# Smart_Driver_Circuit.net
KiCad netlist of a schematic drawn in Altium Designer
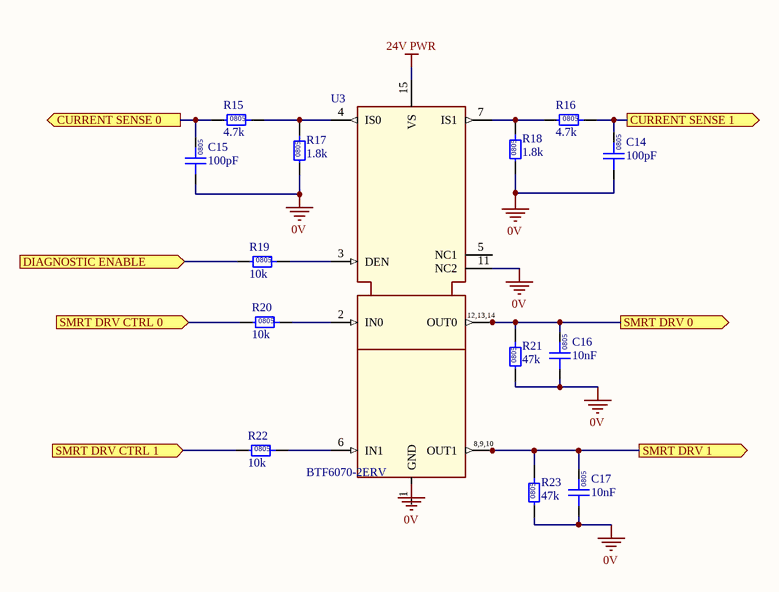
[diagram p0: Smart Driver Circuit.SchDoc]

(export (version "E")
  (design (tool "Eeschema 10.0.6"))
  (components
    (comp (ref "C14")
      (value "100pF")
      (footprint "0805")
      (fields
        (field (name "PART NUMBER") "GCM2165C1H101JA16D")
        (field (name "MANUFACTURER") "muRata")
        (field (name "TOLERANCE") "±5%")
      )
      (libsource (lib "ts_standard_library") (part "Capacitor 0805"))
    )
    (comp (ref "C15")
      (value "100pF")
      (footprint "0805")
      (fields
        (field (name "PART NUMBER") "GCM2165C1H101JA16D")
        (field (name "MANUFACTURER") "muRata")
        (field (name "TOLERANCE") "±5%")
      )
      (libsource (lib "ts_standard_library") (part "Capacitor 0805"))
    )
    (comp (ref "C16")
      (value "10nF")
      (footprint "0805")
      (fields
        (field (name "PART NUMBER") "GCM2195C1H103JA16D")
        (field (name "MANUFACTURER") "muRata")
        (field (name "TOLERANCE") "±5%")
      )
      (libsource (lib "ts_standard_library") (part "Capacitor 0805"))
    )
    (comp (ref "C17")
      (value "10nF")
      (footprint "0805")
      (fields
        (field (name "PART NUMBER") "GCM2195C1H103JA16D")
        (field (name "MANUFACTURER") "muRata")
        (field (name "TOLERANCE") "±5%")
      )
      (libsource (lib "ts_standard_library") (part "Capacitor 0805"))
    )
    (comp (ref "R15")
      (value "4.7k")
      (footprint "0805")
      (fields
        (field (name "PART NUMBER") "RC0805FR074K7L")
        (field (name "MANUFACTURER") "YAGEO")
        (field (name "TOLERANCE") "0.01")
      )
      (libsource (lib "ts_standard_library") (part "Resistor 0805"))
    )
    (comp (ref "R16")
      (value "4.7k")
      (footprint "0805")
      (fields
        (field (name "PART NUMBER") "RC0805FR074K7L")
        (field (name "MANUFACTURER") "YAGEO")
        (field (name "TOLERANCE") "0.01")
      )
      (libsource (lib "ts_standard_library") (part "Resistor 0805"))
    )
    (comp (ref "R17")
      (value "1.8k")
      (footprint "0805")
      (fields
        (field (name "PART NUMBER") "RC0805FR071K8L")
        (field (name "MANUFACTURER") "YAGEO")
        (field (name "TOLERANCE") "0.01")
      )
      (libsource (lib "ts_standard_library") (part "Resistor 0805"))
    )
    (comp (ref "R18")
      (value "1.8k")
      (footprint "0805")
      (fields
        (field (name "PART NUMBER") "RC0805FR071K8L")
        (field (name "MANUFACTURER") "YAGEO")
        (field (name "TOLERANCE") "0.01")
      )
      (libsource (lib "ts_standard_library") (part "Resistor 0805"))
    )
    (comp (ref "R19")
      (value "10k")
      (footprint "0805")
      (fields
        (field (name "PART NUMBER") "RC0805FR0710KL")
        (field (name "MANUFACTURER") "YAGEO")
        (field (name "TOLERANCE") "0.01")
      )
      (libsource (lib "ts_standard_library") (part "Resistor 0805"))
    )
    (comp (ref "R20")
      (value "10k")
      (footprint "0805")
      (fields
        (field (name "PART NUMBER") "RC0805FR0710KL")
        (field (name "MANUFACTURER") "YAGEO")
        (field (name "TOLERANCE") "0.01")
      )
      (libsource (lib "ts_standard_library") (part "Resistor 0805"))
    )
    (comp (ref "R21")
      (value "47k")
      (footprint "0805")
      (fields
        (field (name "PART NUMBER") "RC0805FR0747KL")
        (field (name "MANUFACTURER") "YAGEO")
        (field (name "TOLERANCE") "0.01")
      )
      (libsource (lib "ts_standard_library") (part "Resistor 0805"))
    )
    (comp (ref "R22")
      (value "10k")
      (footprint "0805")
      (fields
        (field (name "PART NUMBER") "RC0805FR0710KL")
        (field (name "MANUFACTURER") "YAGEO")
        (field (name "TOLERANCE") "0.01")
      )
      (libsource (lib "ts_standard_library") (part "Resistor 0805"))
    )
    (comp (ref "R23")
      (value "47k")
      (footprint "0805")
      (fields
        (field (name "PART NUMBER") "RC0805FR0747KL")
        (field (name "MANUFACTURER") "YAGEO")
        (field (name "TOLERANCE") "0.01")
      )
      (libsource (lib "ts_standard_library") (part "Resistor 0805"))
    )
    (comp (ref "U3")
      (value "BTF6070-2ERV")
      (footprint "SOIC127P600X115-15N-V1")
      (description "Smart High-Side Power Switch, Dual Channel")
      (fields
        (field (name "MANUFACTURER") "Infineon Technologies")
        (field (name "PART NUMBER") "BTF60702ERVXUMA1")
      )
      (libsource (lib "ts_standard_library") (part "BTF6070-2ERV"))
    )
  )
  (nets
    (net (code "1") (name "/CURRENT SENSE 0") (class "Default")
      (node (ref "C15") (pin "2") (pinfunction "2_2") (pintype "passive"))
      (node (ref "R15") (pin "1") (pinfunction "1_1") (pintype "passive"))
    )
    (net (code "2") (name "/CURRENT SENSE 1") (class "Default")
      (node (ref "C14") (pin "2") (pinfunction "2_2") (pintype "passive"))
      (node (ref "R16") (pin "2") (pinfunction "2_2") (pintype "passive"))
    )
    (net (code "3") (name "/DIAGNOSTIC ENABLE") (class "Default")
      (node (ref "R19") (pin "1") (pinfunction "1_1") (pintype "passive"))
    )
    (net (code "4") (name "/SMRT DRV 0") (class "Default")
      (node (ref "C16") (pin "2") (pinfunction "2_2") (pintype "passive"))
      (node (ref "R21") (pin "2") (pinfunction "2_2") (pintype "passive"))
      (node (ref "U3") (pin "12") (pinfunction "OUT0_12") (pintype "output"))
      (node (ref "U3") (pin "13") (pinfunction "OUT0_13") (pintype "output"))
      (node (ref "U3") (pin "14") (pinfunction "OUT0_14") (pintype "output"))
    )
    (net (code "5") (name "/SMRT DRV 1") (class "Default")
      (node (ref "C17") (pin "2") (pinfunction "2_2") (pintype "passive"))
      (node (ref "R23") (pin "2") (pinfunction "2_2") (pintype "passive"))
      (node (ref "U3") (pin "10") (pinfunction "OUT1_10") (pintype "output"))
      (node (ref "U3") (pin "8") (pinfunction "OUT1_8") (pintype "output"))
      (node (ref "U3") (pin "9") (pinfunction "OUT1_9") (pintype "output"))
    )
    (net (code "6") (name "/SMRT DRV CTRL 0") (class "Default")
      (node (ref "R20") (pin "1") (pinfunction "1_1") (pintype "passive"))
    )
    (net (code "7") (name "/SMRT DRV CTRL 1") (class "Default")
      (node (ref "R22") (pin "1") (pinfunction "1_1") (pintype "passive"))
    )
    (net (code "8") (name "0V") (class "Default")
      (node (ref "C14") (pin "1") (pinfunction "1_1") (pintype "passive"))
      (node (ref "C15") (pin "1") (pinfunction "1_1") (pintype "passive"))
      (node (ref "C16") (pin "1") (pinfunction "1_1") (pintype "passive"))
      (node (ref "C17") (pin "1") (pinfunction "1_1") (pintype "passive"))
      (node (ref "R17") (pin "1") (pinfunction "1_1") (pintype "passive"))
      (node (ref "R18") (pin "1") (pinfunction "1_1") (pintype "passive"))
      (node (ref "R21") (pin "1") (pinfunction "1_1") (pintype "passive"))
      (node (ref "R23") (pin "1") (pinfunction "1_1") (pintype "passive"))
      (node (ref "U3") (pin "11") (pinfunction "NC2_11") (pintype "passive"))
    )
    (net (code "9") (name "24V PWR") (class "Default")
      (node (ref "U3") (pin "15") (pinfunction "VS_15") (pintype "power_in"))
    )
    (net (code "10") (name "Net-(U3-DEN)") (class "Default")
      (node (ref "R19") (pin "2") (pinfunction "2_2") (pintype "passive"))
      (node (ref "U3") (pin "3") (pinfunction "DEN_3") (pintype "input"))
    )
    (net (code "11") (name "Net-(U3-IN0)") (class "Default")
      (node (ref "R20") (pin "2") (pinfunction "2_2") (pintype "passive"))
      (node (ref "U3") (pin "2") (pinfunction "IN0_2") (pintype "input"))
    )
    (net (code "12") (name "Net-(U3-IN1)") (class "Default")
      (node (ref "R22") (pin "2") (pinfunction "2_2") (pintype "passive"))
      (node (ref "U3") (pin "6") (pinfunction "IN1_6") (pintype "input"))
    )
    (net (code "13") (name "Net-(U3-IS0)") (class "Default")
      (node (ref "R15") (pin "2") (pinfunction "2_2") (pintype "passive"))
      (node (ref "R17") (pin "2") (pinfunction "2_2") (pintype "passive"))
      (node (ref "U3") (pin "4") (pinfunction "IS0_4") (pintype "output"))
    )
    (net (code "14") (name "Net-(U3-IS1)") (class "Default")
      (node (ref "R16") (pin "1") (pinfunction "1_1") (pintype "passive"))
      (node (ref "R18") (pin "2") (pinfunction "2_2") (pintype "passive"))
      (node (ref "U3") (pin "7") (pinfunction "IS1_7") (pintype "output"))
    )
    (net (code "15") (name "unconnected-(U3-GND-Pad1)") (class "Default")
      (node (ref "U3") (pin "1") (pinfunction "GND_1") (pintype "power_in"))
    )
    (net (code "16") (name "unconnected-(U3-NC1-Pad5)") (class "Default")
      (node (ref "U3") (pin "5") (pinfunction "NC1_5") (pintype "passive"))
    )
  )
)
